# LDO_12V-5V.net
KiCad netlist of a schematic drawn in Altium Designer
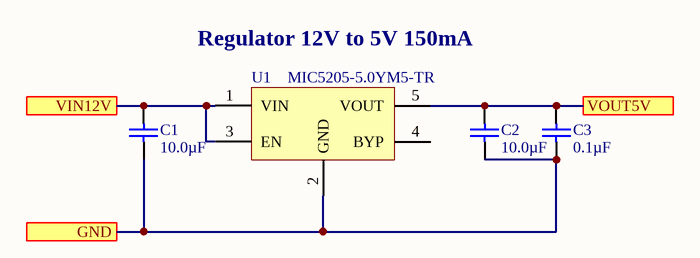
[diagram p0: LDO_12V-5V.SchDoc]

(export (version "E")
  (design (tool "Eeschema 10.0.6"))
  (components
    (comp (ref "C1")
      (value "10.0µF")
      (footprint "PCB-j0jk5xr8qbnaskonccg4-1")
      (description "CAP CER 10uF ±10% 25V X7R 1210")
      (fields
        (field (name "MANUFACTURER") "TDK")
        (field (name "MANUFACTURERPARTNUMBER") "C3225X7R1E106K250AC")
      )
      (libsource (lib "DST800_NMEA2k-CAN_Indicator") (part "CMP-2bdce35de069f41b-1"))
    )
    (comp (ref "C2")
      (value "10.0µF")
      (footprint "PCB-j0jk5xr8qbnaskonccg4-1")
      (description "CAP CER 10uF ±10% 25V X7R 1210")
      (fields
        (field (name "MANUFACTURER") "TDK")
        (field (name "MANUFACTURERPARTNUMBER") "C3225X7R1E106K250AC")
      )
      (libsource (lib "DST800_NMEA2k-CAN_Indicator") (part "CMP-2bdce35de069f41b-1"))
    )
    (comp (ref "C3")
      (value "0.1µF")
      (footprint "PCB-mhhqftc5ilnrg4qi8ds6-1")
      (description "CAP CER 0.1uF 50V X7R 0603")
      (fields
        (field (name "MANUFACTURER") "Samsung Electro-Mechanics")
        (field (name "MANUFACTURERPARTNUMBER") "CL10B104KB8NNNC")
      )
      (libsource (lib "DST800_NMEA2k-CAN_Indicator") (part "CMP-1af8d38ac64bc53f-5"))
    )
    (comp (ref "U1")
      (value "MIC5205-5.0YM5-TR")
      (footprint "SOT-23-5_N")
      (description "IC Regulator LDO 5 V Fixed Output 150 mA SOT-23-5")
      (fields (field (name "MANUFACTURER") "Microchip"))
      (libsource (lib "DST800_NMEA2k-CAN_Indicator") (part "CMP-6255a8a416e5bd92-5"))
    )
  )
  (nets
    (net (code "1") (name "/GND") (class "Default")
      (node (ref "C1") (pin "1") (pinfunction "1_1") (pintype "passive"))
      (node (ref "C2") (pin "1") (pinfunction "1_1") (pintype "passive"))
      (node (ref "C3") (pin "1") (pinfunction "1_1") (pintype "passive"))
      (node (ref "U1") (pin "2") (pinfunction "GND_2") (pintype "passive"))
    )
    (net (code "2") (name "/VIN12V") (class "Default")
      (node (ref "C1") (pin "2") (pinfunction "2_2") (pintype "passive"))
      (node (ref "U1") (pin "1") (pinfunction "VIN_1") (pintype "passive"))
      (node (ref "U1") (pin "3") (pinfunction "EN_3") (pintype "passive"))
    )
    (net (code "3") (name "/VOUT5V") (class "Default")
      (node (ref "C2") (pin "2") (pinfunction "2_2") (pintype "passive"))
      (node (ref "C3") (pin "2") (pinfunction "2_2") (pintype "passive"))
      (node (ref "U1") (pin "5") (pinfunction "VOUT_5") (pintype "passive"))
    )
    (net (code "4") (name "unconnected-(U1-BYP-Pad4)") (class "Default")
      (node (ref "U1") (pin "4") (pinfunction "BYP_4") (pintype "passive"))
    )
  )
)
